# st_v1.net
KiCad netlist of a schematic drawn in Altium Designer
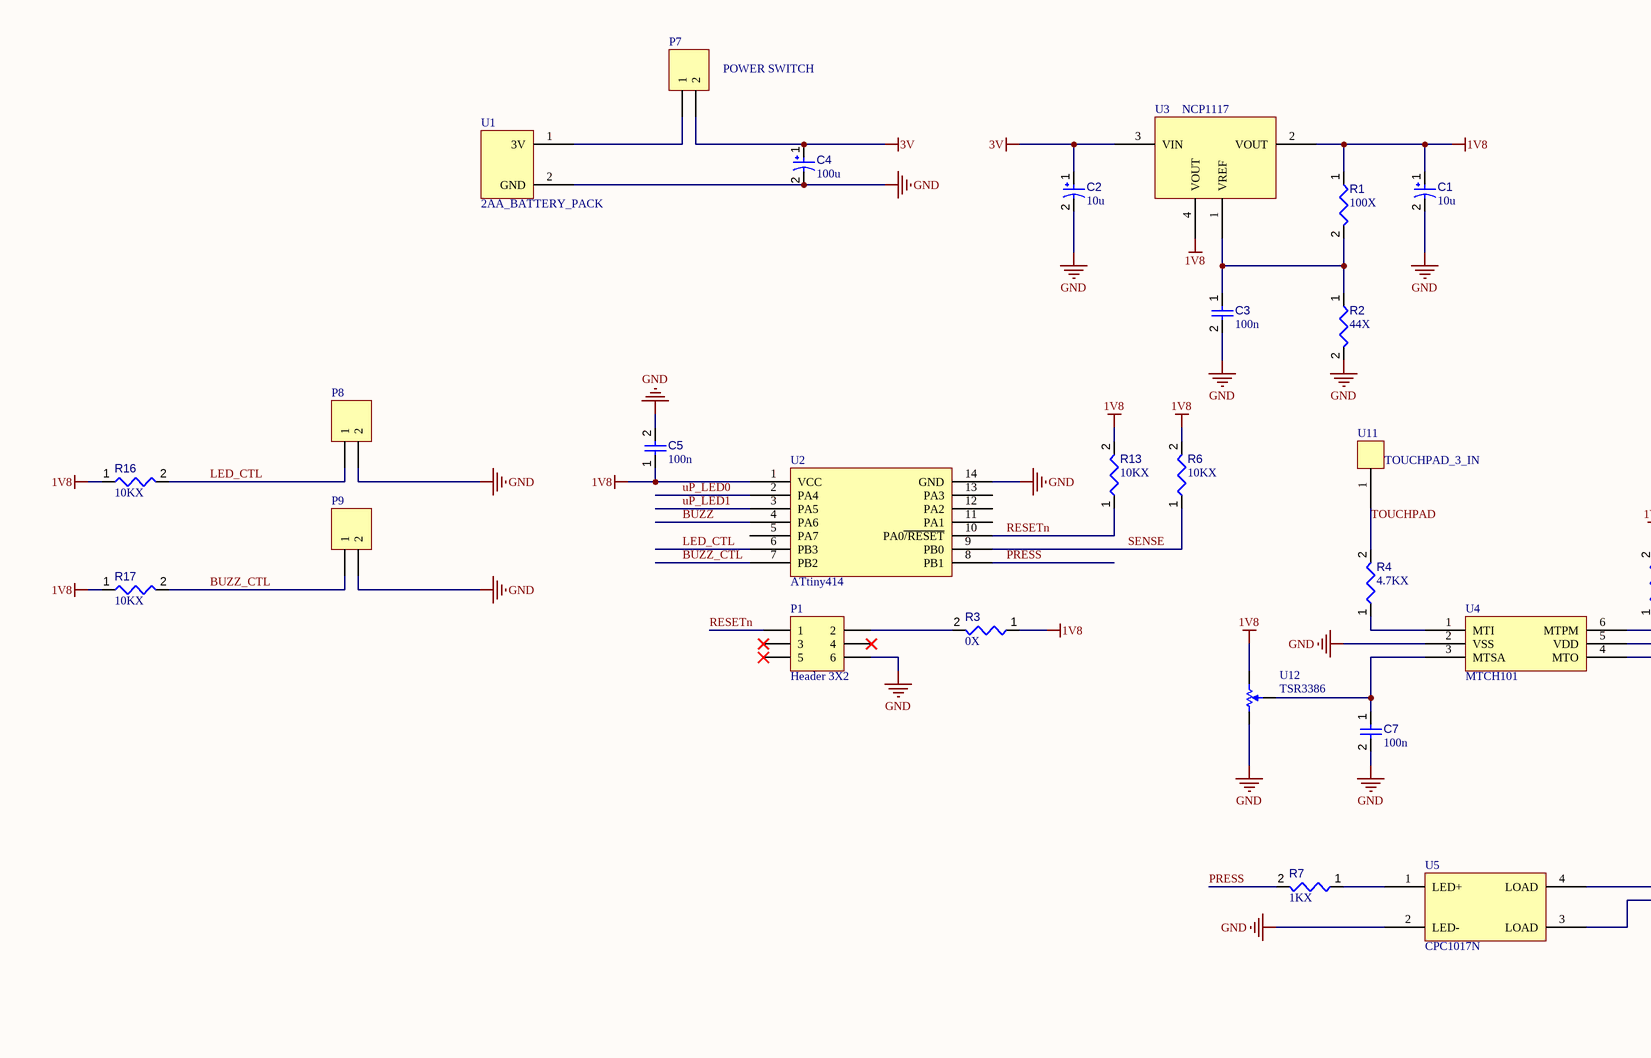
[diagram p0: st_v1.SchDoc, left]
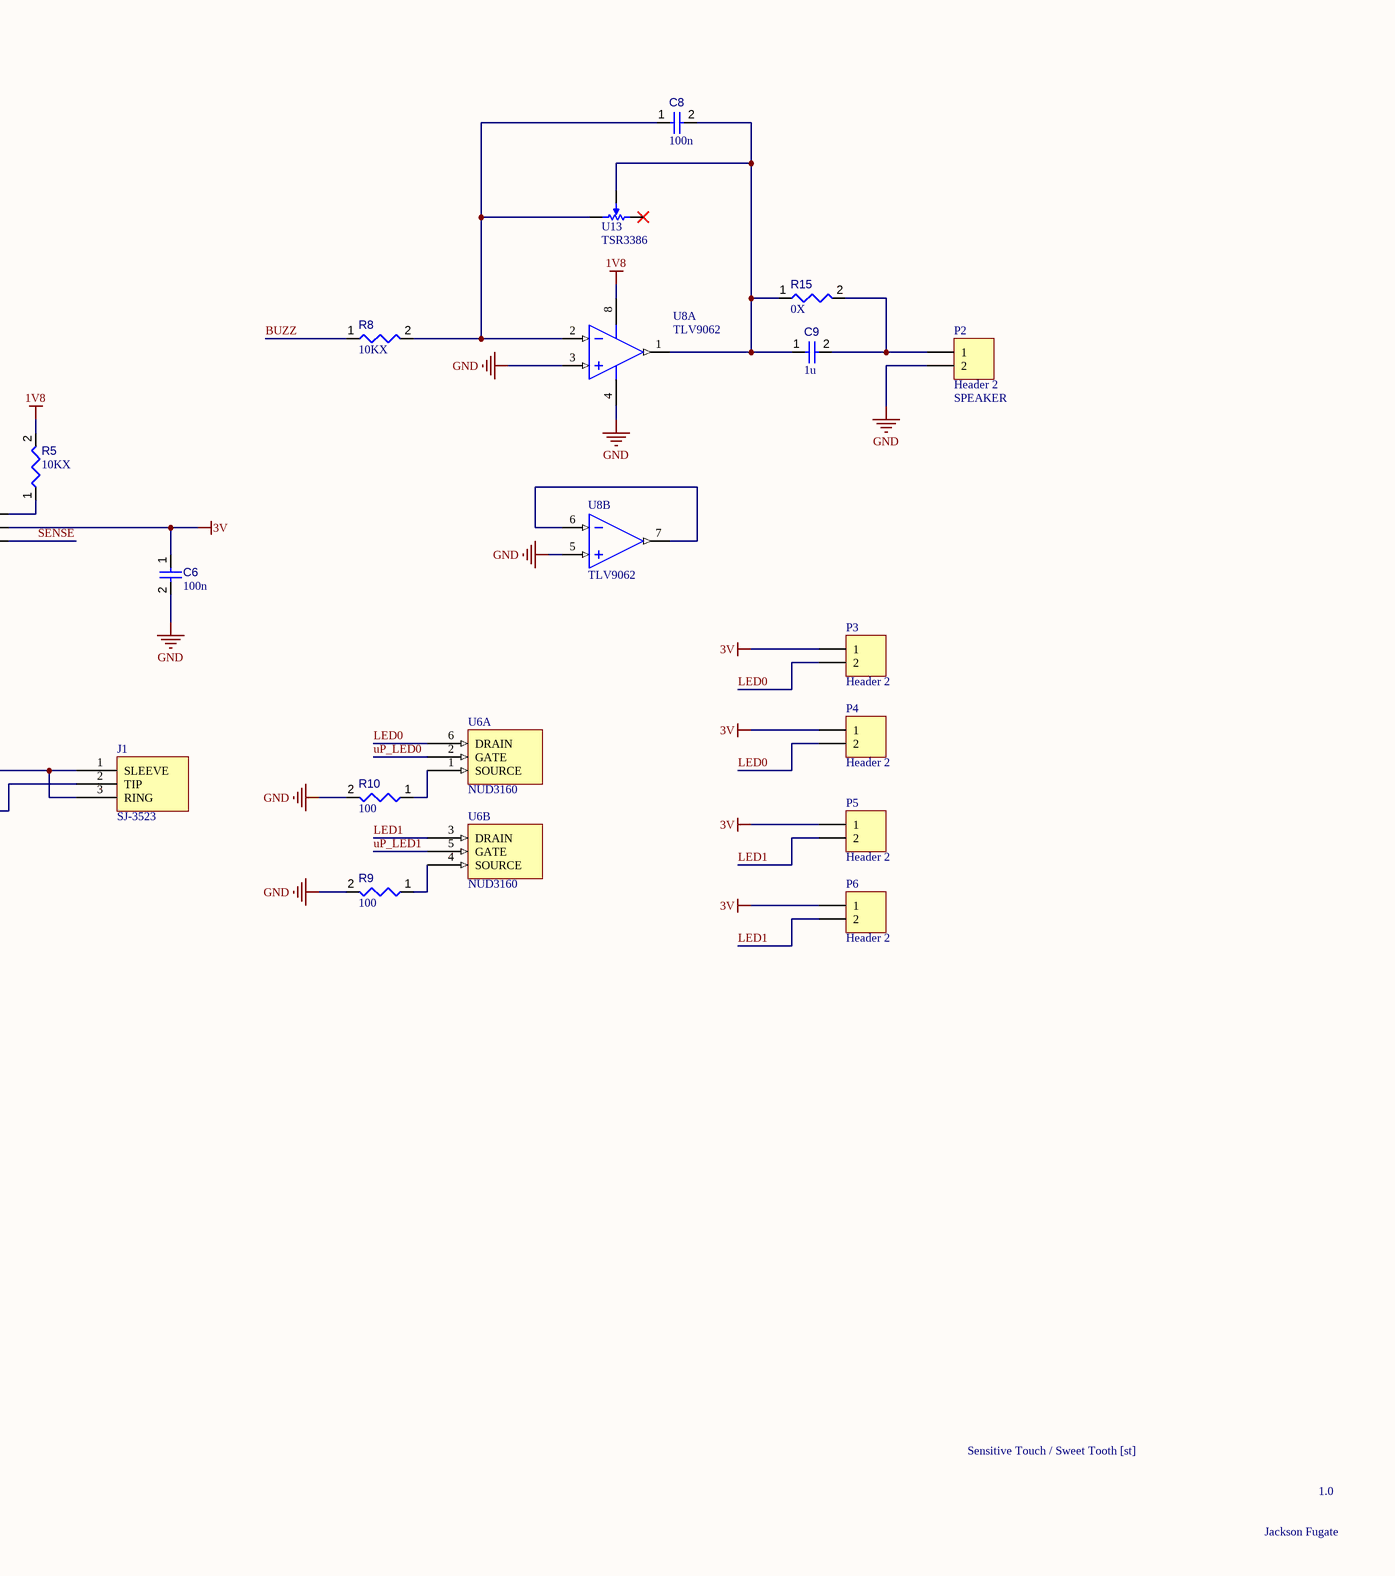
[diagram p1: st_v1.SchDoc, right]

(export (version "E")
  (design (tool "Eeschema 10.0.6"))
  (components
    (comp (ref "C1")
      (value "10u")
      (footprint "CAPPR65-350-1150X800X1250")
      (description "Aluminum Electrolytic Capacitor, 47 uF, +/- 20%, 100 V, -40 to 85 degC, 2-Pin THD, RoHS, Bulk")
      (fields (field (name "TOLERANCE") "20%") (field (name "MANUFACTURER") "Panasonic"))
      (libsource (lib "Jackson Fugate") (part "CAP-P-2"))
    )
    (comp (ref "C2")
      (value "10u")
      (footprint "CAPPR65-350-1150X800X1250")
      (description "Aluminum Electrolytic Capacitor, 47 uF, +/- 20%, 100 V, -40 to 85 degC, 2-Pin THD, RoHS, Bulk")
      (fields (field (name "TOLERANCE") "20%") (field (name "MANUFACTURER") "Panasonic"))
      (libsource (lib "Jackson Fugate") (part "CAP-P-2"))
    )
    (comp (ref "C3")
      (value "100n")
      (footprint "CAPC2013X135X45NL10T25")
      (description "Chip Capacitor, 10 uF, +/- 10%, 16 V, 0805 (2012 Metric)")
      (fields (field (name "TOLERANCE") "10%") (field (name "Comment") "Capacitor 10 uF +/- 10% 16 V 0805"))
      (libsource (lib "Jackson Fugate") (part "CAP-NP-2"))
    )
    (comp (ref "C4")
      (value "100u")
      (footprint "CAPPR65-350-1150X800X1250")
      (description "Aluminum Electrolytic Capacitor, 47 uF, +/- 20%, 100 V, -40 to 85 degC, 2-Pin THD, RoHS, Bulk")
      (fields (field (name "TOLERANCE") "20%") (field (name "MANUFACTURER") "Panasonic"))
      (libsource (lib "Jackson Fugate") (part "CAP-P-2"))
    )
    (comp (ref "C5")
      (value "100n")
      (footprint "CAPC2013X135X45NL10T25")
      (description "Chip Capacitor, 10 uF, +/- 10%, 16 V, 0805 (2012 Metric)")
      (fields (field (name "TOLERANCE") "10%") (field (name "Comment") "Capacitor 10 uF +/- 10% 16 V 0805"))
      (libsource (lib "Jackson Fugate") (part "CAP-NP-2"))
    )
    (comp (ref "C6")
      (value "100n")
      (footprint "CAPC2013X135X45NL10T25")
      (description "Chip Capacitor, 10 uF, +/- 10%, 16 V, 0805 (2012 Metric)")
      (fields (field (name "TOLERANCE") "10%") (field (name "Comment") "Capacitor 10 uF +/- 10% 16 V 0805"))
      (libsource (lib "Jackson Fugate") (part "CAP-NP-2"))
    )
    (comp (ref "C7")
      (value "100n")
      (footprint "CAPC2013X135X45NL10T25")
      (description "Chip Capacitor, 10 uF, +/- 10%, 16 V, 0805 (2012 Metric)")
      (fields (field (name "TOLERANCE") "10%") (field (name "Comment") "Capacitor 10 uF +/- 10% 16 V 0805"))
      (libsource (lib "Jackson Fugate") (part "CAP-NP-2"))
    )
    (comp (ref "C8")
      (value "100n")
      (footprint "CAPC2013X135X45NL10T25")
      (description "Chip Capacitor, 10 uF, +/- 10%, 16 V, 0805 (2012 Metric)")
      (fields (field (name "TOLERANCE") "10%") (field (name "Comment") "Capacitor 10 uF +/- 10% 16 V 0805"))
      (libsource (lib "Jackson Fugate") (part "CAP-NP-2"))
    )
    (comp (ref "C9")
      (value "1u")
      (footprint "CAPC2013X135X45NL10T25")
      (description "Chip Capacitor, 10 uF, +/- 10%, 16 V, 0805 (2012 Metric)")
      (fields (field (name "TOLERANCE") "10%") (field (name "Comment") "Capacitor 10 uF +/- 10% 16 V 0805"))
      (libsource (lib "Jackson Fugate") (part "CAP-NP-2"))
    )
    (comp (ref "J1")
      (value "SJ-3523")
      (footprint "SJ-352X")
      (libsource (lib "JF_master_lib") (part "SJ-3523"))
    )
    (comp (ref "P1")
      (value "Header 3X2")
      (footprint "HDR2X3")
      (description "Header, 3-Pin, Dual row")
      (fields (field (name "PUBLISHER") "Altium Limited"))
      (libsource (lib "Jackson Fugate") (part "Header 3X2H"))
    )
    (comp (ref "P2")
      (value "Header 2")
      (footprint "HDR1X2")
      (description "Header, 2-Pin")
      (fields (field (name "PUBLISHER") "Altium Limited"))
      (libsource (lib "Jackson Fugate") (part "Header 2H"))
    )
    (comp (ref "P3")
      (value "Header 2")
      (footprint "HDR1X2")
      (description "Header, 2-Pin")
      (fields (field (name "PUBLISHER") "Altium Limited"))
      (libsource (lib "Jackson Fugate") (part "Header 2H"))
    )
    (comp (ref "P4")
      (value "Header 2")
      (footprint "HDR1X2")
      (description "Header, 2-Pin")
      (fields (field (name "PUBLISHER") "Altium Limited"))
      (libsource (lib "Jackson Fugate") (part "Header 2H"))
    )
    (comp (ref "P5")
      (value "Header 2")
      (footprint "HDR1X2")
      (description "Header, 2-Pin")
      (fields (field (name "PUBLISHER") "Altium Limited"))
      (libsource (lib "Jackson Fugate") (part "Header 2H"))
    )
    (comp (ref "P6")
      (value "Header 2")
      (footprint "HDR1X2")
      (description "Header, 2-Pin")
      (fields (field (name "PUBLISHER") "Altium Limited"))
      (libsource (lib "Jackson Fugate") (part "Header 2H"))
    )
    (comp (ref "P7")
      (value "POWER SWITCH")
      (footprint "HDR1X2")
      (description "Header, 2-Pin")
      (fields (field (name "PUBLISHER") "Altium Limited"))
      (libsource (lib "") (part "Header 2H_1"))
    )
    (comp (ref "P8")
      (value "POWER SWITCH")
      (footprint "HDR1X2")
      (description "Header, 2-Pin")
      (fields (field (name "PUBLISHER") "Altium Limited"))
      (libsource (lib "") (part "Header 2H_1"))
    )
    (comp (ref "P9")
      (value "POWER SWITCH")
      (footprint "HDR1X2")
      (description "Header, 2-Pin")
      (fields (field (name "PUBLISHER") "Altium Limited"))
      (libsource (lib "") (part "Header 2H_1"))
    )
    (comp (ref "R1")
      (value "100X")
      (footprint "RESC0805(2012)_L")
      (description "1K 0.125W 5% 0805 (2012 Metric)  SMD")
      (fields (field (name "POWER") "0.125W") (field (name "TOLERANCE") "5%"))
      (libsource (lib "Jackson Fugate") (part "1KR5J"))
    )
    (comp (ref "R2")
      (value "44X")
      (footprint "RESC0805(2012)_L")
      (description "1K 0.125W 5% 0805 (2012 Metric)  SMD")
      (fields (field (name "POWER") "0.125W") (field (name "TOLERANCE") "5%"))
      (libsource (lib "Jackson Fugate") (part "1KR5J"))
    )
    (comp (ref "R3")
      (value "0X")
      (footprint "RESC0805(2012)_L")
      (description "1K 0.125W 5% 0805 (2012 Metric)  SMD")
      (fields (field (name "POWER") "0.125W") (field (name "TOLERANCE") "5%"))
      (libsource (lib "Jackson Fugate") (part "1KR5J"))
    )
    (comp (ref "R4")
      (value "4.7KX")
      (footprint "RESC0805(2012)_L")
      (description "1K 0.125W 5% 0805 (2012 Metric)  SMD")
      (fields (field (name "POWER") "0.125W") (field (name "TOLERANCE") "5%"))
      (libsource (lib "Jackson Fugate") (part "1KR5J"))
    )
    (comp (ref "R5")
      (value "10KX")
      (footprint "RESC0805(2012)_L")
      (description "1K 0.125W 5% 0805 (2012 Metric)  SMD")
      (fields (field (name "POWER") "0.125W") (field (name "TOLERANCE") "5%"))
      (libsource (lib "Jackson Fugate") (part "1KR5J"))
    )
    (comp (ref "R6")
      (value "10KX")
      (footprint "RESC0805(2012)_L")
      (description "1K 0.125W 5% 0805 (2012 Metric)  SMD")
      (fields (field (name "POWER") "0.125W") (field (name "TOLERANCE") "5%"))
      (libsource (lib "Jackson Fugate") (part "1KR5J"))
    )
    (comp (ref "R7")
      (value "1KX")
      (footprint "RESC0805(2012)_L")
      (description "1K 0.125W 5% 0805 (2012 Metric)  SMD")
      (fields (field (name "POWER") "0.125W") (field (name "TOLERANCE") "5%"))
      (libsource (lib "Jackson Fugate") (part "1KR5J"))
    )
    (comp (ref "R8")
      (value "10KX")
      (footprint "RESC0805(2012)_L")
      (description "1K 0.125W 5% 0805 (2012 Metric)  SMD")
      (fields (field (name "POWER") "0.125W") (field (name "TOLERANCE") "5%"))
      (libsource (lib "Jackson Fugate") (part "1KR5J"))
    )
    (comp (ref "R9")
      (value "100")
      (footprint "RESC0805(2012)_L")
      (description "1K 0.125W 5% 0805 (2012 Metric)  SMD")
      (fields (field (name "POWER") "0.125W") (field (name "TOLERANCE") "5%"))
      (libsource (lib "Jackson Fugate") (part "1KR5J"))
    )
    (comp (ref "R10")
      (value "100")
      (footprint "RESC0805(2012)_L")
      (description "1K 0.125W 5% 0805 (2012 Metric)  SMD")
      (fields (field (name "POWER") "0.125W") (field (name "TOLERANCE") "5%"))
      (libsource (lib "Jackson Fugate") (part "1KR5J"))
    )
    (comp (ref "R13")
      (value "10KX")
      (footprint "RESC0805(2012)_L")
      (description "1K 0.125W 5% 0805 (2012 Metric)  SMD")
      (fields (field (name "POWER") "0.125W") (field (name "TOLERANCE") "5%"))
      (libsource (lib "Jackson Fugate") (part "1KR5J"))
    )
    (comp (ref "R15")
      (value "0X")
      (footprint "RESC0805(2012)_L")
      (description "1K 0.125W 5% 0805 (2012 Metric)  SMD")
      (fields (field (name "POWER") "0.125W") (field (name "TOLERANCE") "5%"))
      (libsource (lib "Jackson Fugate") (part "1KR5J"))
    )
    (comp (ref "R16")
      (value "10KX")
      (footprint "RESC0805(2012)_L")
      (description "1K 0.125W 5% 0805 (2012 Metric)  SMD")
      (fields (field (name "POWER") "0.125W") (field (name "TOLERANCE") "5%"))
      (libsource (lib "Jackson Fugate") (part "1KR5J"))
    )
    (comp (ref "R17")
      (value "10KX")
      (footprint "RESC0805(2012)_L")
      (description "1K 0.125W 5% 0805 (2012 Metric)  SMD")
      (fields (field (name "POWER") "0.125W") (field (name "TOLERANCE") "5%"))
      (libsource (lib "Jackson Fugate") (part "1KR5J"))
    )
    (comp (ref "U1")
      (value "2AA_BATTERY_PACK")
      (footprint "2AA_BATTERY_PACK")
      (libsource (lib "JF_master_lib") (part "2AA_BATTERY_PACK"))
    )
    (comp (ref "U2")
      (value "ATtiny414")
      (footprint "SOIC-14")
      (libsource (lib "JF_master_lib") (part "ATtiny414"))
    )
    (comp (ref "U3")
      (value "NCP1117")
      (footprint "SOT-223")
      (libsource (lib "JF_master_lib") (part "NCP1117"))
    )
    (comp (ref "U4")
      (value "MTCH101")
      (footprint "SOT-23-6")
      (libsource (lib "JF_master_lib") (part "MTCH101"))
    )
    (comp (ref "U5")
      (value "CPC1017N")
      (footprint "CPC1017N")
      (libsource (lib "JF_master_lib") (part "CPC1017N"))
    )
    (comp (ref "U6") (value "NUD3160") (footprint "SC-74") (libsource (lib "JF_master_lib") (part "NUD3160")))
    (comp (ref "U8")
      (value "TLV9062")
      (footprint "SOIC-8")
      (libsource (lib "JF_master_lib") (part "TLV9062"))
    )
    (comp (ref "U11")
      (value "TOUCHPAD_3_IN")
      (footprint "TOUCHPAD_3_IN")
      (libsource (lib "JF_master_lib") (part "TOUCHPAD_3_IN"))
    )
    (comp (ref "U12")
      (value "TSR3386")
      (footprint "TSR3386")
      (libsource (lib "JF_master_lib") (part "TSR3386"))
    )
    (comp (ref "U13")
      (value "TSR3386")
      (footprint "TSR3386")
      (libsource (lib "JF_master_lib") (part "TSR3386"))
    )
  )
  (nets
    (net (code "1") (name "/BUZZ") (class "Default")
      (node (ref "R8") (pin "1") (pinfunction "1_1") (pintype "passive"))
      (node (ref "U2") (pin "4") (pinfunction "PA6_4") (pintype "passive"))
    )
    (net (code "2") (name "/BUZZ_CTL") (class "Default")
      (node (ref "P9") (pin "1") (pinfunction "1_1") (pintype "passive"))
      (node (ref "R17") (pin "2") (pinfunction "2_2") (pintype "passive"))
      (node (ref "U2") (pin "7") (pinfunction "PB2_7") (pintype "passive"))
    )
    (net (code "3") (name "/LED0") (class "Default")
      (node (ref "P3") (pin "2") (pinfunction "2_2") (pintype "passive"))
      (node (ref "P4") (pin "2") (pinfunction "2_2") (pintype "passive"))
      (node (ref "U6") (pin "6") (pinfunction "DRAIN_6") (pintype "input"))
    )
    (net (code "4") (name "/LED1") (class "Default")
      (node (ref "P5") (pin "2") (pinfunction "2_2") (pintype "passive"))
      (node (ref "P6") (pin "2") (pinfunction "2_2") (pintype "passive"))
      (node (ref "U6") (pin "3") (pinfunction "DRAIN_3") (pintype "input"))
    )
    (net (code "5") (name "/LED_CTL") (class "Default")
      (node (ref "P8") (pin "1") (pinfunction "1_1") (pintype "passive"))
      (node (ref "R16") (pin "2") (pinfunction "2_2") (pintype "passive"))
      (node (ref "U2") (pin "6") (pinfunction "PB3_6") (pintype "passive"))
    )
    (net (code "6") (name "/PRESS") (class "Default")
      (node (ref "R7") (pin "2") (pinfunction "2_2") (pintype "passive"))
      (node (ref "U2") (pin "8") (pinfunction "PB1_8") (pintype "passive"))
    )
    (net (code "7") (name "/RESETn") (class "Default")
      (node (ref "P1") (pin "1") (pinfunction "1_1") (pintype "passive"))
      (node (ref "R13") (pin "1") (pinfunction "1_1") (pintype "passive"))
      (node (ref "U2") (pin "10") (pinfunction "PA0~{/RESET}_10") (pintype "passive"))
    )
    (net (code "8") (name "/SENSE") (class "Default")
      (node (ref "R6") (pin "1") (pinfunction "1_1") (pintype "passive"))
      (node (ref "U2") (pin "9") (pinfunction "PB0_9") (pintype "passive"))
      (node (ref "U4") (pin "4") (pinfunction "MTO_4") (pintype "passive"))
    )
    (net (code "9") (name "/TOUCHPAD") (class "Default")
      (node (ref "R4") (pin "2") (pinfunction "2_2") (pintype "passive"))
      (node (ref "U11") (pin "1") (pintype "passive"))
    )
    (net (code "10") (name "/uP_LED0") (class "Default")
      (node (ref "U2") (pin "2") (pinfunction "PA4_2") (pintype "passive"))
      (node (ref "U6") (pin "2") (pinfunction "GATE_2") (pintype "input"))
    )
    (net (code "11") (name "/uP_LED1") (class "Default")
      (node (ref "U2") (pin "3") (pinfunction "PA5_3") (pintype "passive"))
      (node (ref "U6") (pin "5") (pinfunction "GATE_5") (pintype "input"))
    )
    (net (code "12") (name "1V8") (class "Default")
      (node (ref "C1") (pin "1") (pinfunction "1_1") (pintype "passive"))
      (node (ref "C5") (pin "1") (pinfunction "1_1") (pintype "passive"))
      (node (ref "R1") (pin "1") (pinfunction "1_1") (pintype "passive"))
      (node (ref "R13") (pin "2") (pinfunction "2_2") (pintype "passive"))
      (node (ref "R16") (pin "1") (pinfunction "1_1") (pintype "passive"))
      (node (ref "R17") (pin "1") (pinfunction "1_1") (pintype "passive"))
      (node (ref "R3") (pin "1") (pinfunction "1_1") (pintype "passive"))
      (node (ref "R5") (pin "2") (pinfunction "2_2") (pintype "passive"))
      (node (ref "R6") (pin "2") (pinfunction "2_2") (pintype "passive"))
      (node (ref "U12") (pin "1") (pinfunction "B_1") (pintype "passive"))
      (node (ref "U2") (pin "1") (pinfunction "VCC_1") (pintype "power_in"))
      (node (ref "U3") (pin "2") (pinfunction "VOUT_2") (pintype "power_in"))
      (node (ref "U3") (pin "4") (pinfunction "VOUT_4") (pintype "power_in"))
      (node (ref "U8") (pin "8") (pinfunction "V+_8") (pintype "power_in"))
    )
    (net (code "13") (name "3V") (class "Default")
      (node (ref "C2") (pin "1") (pinfunction "1_1") (pintype "passive"))
      (node (ref "C4") (pin "1") (pinfunction "1_1") (pintype "passive"))
      (node (ref "C6") (pin "1") (pinfunction "1_1") (pintype "passive"))
      (node (ref "P3") (pin "1") (pinfunction "1_1") (pintype "passive"))
      (node (ref "P4") (pin "1") (pinfunction "1_1") (pintype "passive"))
      (node (ref "P5") (pin "1") (pinfunction "1_1") (pintype "passive"))
      (node (ref "P6") (pin "1") (pinfunction "1_1") (pintype "passive"))
      (node (ref "P7") (pin "2") (pinfunction "2_2") (pintype "passive"))
      (node (ref "U3") (pin "3") (pinfunction "VIN_3") (pintype "power_in"))
      (node (ref "U4") (pin "5") (pinfunction "VDD_5") (pintype "power_in"))
    )
    (net (code "14") (name "GND") (class "Default")
      (node (ref "C1") (pin "2") (pinfunction "2_2") (pintype "passive"))
      (node (ref "C2") (pin "2") (pinfunction "2_2") (pintype "passive"))
      (node (ref "C3") (pin "2") (pinfunction "2_2") (pintype "passive"))
      (node (ref "C4") (pin "2") (pinfunction "2_2") (pintype "passive"))
      (node (ref "C5") (pin "2") (pinfunction "2_2") (pintype "passive"))
      (node (ref "C6") (pin "2") (pinfunction "2_2") (pintype "passive"))
      (node (ref "C7") (pin "2") (pinfunction "2_2") (pintype "passive"))
      (node (ref "P1") (pin "6") (pinfunction "6_6") (pintype "passive"))
      (node (ref "P2") (pin "2") (pinfunction "2_2") (pintype "passive"))
      (node (ref "P8") (pin "2") (pinfunction "2_2") (pintype "passive"))
      (node (ref "P9") (pin "2") (pinfunction "2_2") (pintype "passive"))
      (node (ref "R10") (pin "2") (pinfunction "2_2") (pintype "passive"))
      (node (ref "R2") (pin "2") (pinfunction "2_2") (pintype "passive"))
      (node (ref "R9") (pin "2") (pinfunction "2_2") (pintype "passive"))
      (node (ref "U1") (pin "2") (pinfunction "GND_2") (pintype "power_in"))
      (node (ref "U12") (pin "3") (pinfunction "A_3") (pintype "passive"))
      (node (ref "U2") (pin "14") (pinfunction "GND_14") (pintype "power_in"))
      (node (ref "U4") (pin "2") (pinfunction "VSS_2") (pintype "power_in"))
      (node (ref "U5") (pin "2") (pinfunction "LED-_2") (pintype "passive"))
      (node (ref "U8") (pin "3") (pinfunction "+IN_3") (pintype "input"))
      (node (ref "U8") (pin "4") (pinfunction "V-_4") (pintype "power_in"))
      (node (ref "U8") (pin "5") (pinfunction "+IN_5") (pintype "input"))
    )
    (net (code "15") (name "Net-(C9-Pad2)") (class "Default")
      (node (ref "C9") (pin "2") (pinfunction "2_2") (pintype "passive"))
      (node (ref "P2") (pin "1") (pinfunction "1_1") (pintype "passive"))
      (node (ref "R15") (pin "2") (pinfunction "2_2") (pintype "passive"))
    )
    (net (code "16") (name "Net-(J1-RING)") (class "Default")
      (node (ref "J1") (pin "1") (pinfunction "SLEEVE_1") (pintype "passive"))
      (node (ref "J1") (pin "3") (pinfunction "RING_3") (pintype "passive"))
      (node (ref "U5") (pin "4") (pinfunction "LOAD_4") (pintype "passive"))
    )
    (net (code "17") (name "Net-(J1-TIP)") (class "Default")
      (node (ref "J1") (pin "2") (pinfunction "TIP_2") (pintype "passive"))
      (node (ref "U5") (pin "3") (pinfunction "LOAD_3") (pintype "passive"))
    )
    (net (code "18") (name "Net-(P1-Pad2)") (class "Default")
      (node (ref "P1") (pin "2") (pinfunction "2_2") (pintype "passive"))
      (node (ref "R3") (pin "2") (pinfunction "2_2") (pintype "passive"))
    )
    (net (code "19") (name "Net-(U1-3V)") (class "Default")
      (node (ref "P7") (pin "1") (pinfunction "1_1") (pintype "passive"))
      (node (ref "U1") (pin "1") (pinfunction "3V_1") (pintype "power_in"))
    )
    (net (code "20") (name "Net-(U3-VREF)") (class "Default")
      (node (ref "C3") (pin "1") (pinfunction "1_1") (pintype "passive"))
      (node (ref "R1") (pin "2") (pinfunction "2_2") (pintype "passive"))
      (node (ref "R2") (pin "1") (pinfunction "1_1") (pintype "passive"))
      (node (ref "U3") (pin "1") (pinfunction "VREF_1") (pintype "power_in"))
    )
    (net (code "21") (name "Net-(U4-MTI)") (class "Default")
      (node (ref "R4") (pin "1") (pinfunction "1_1") (pintype "passive"))
      (node (ref "U4") (pin "1") (pinfunction "MTI_1") (pintype "passive"))
    )
    (net (code "22") (name "Net-(U4-MTPM)") (class "Default")
      (node (ref "R5") (pin "1") (pinfunction "1_1") (pintype "passive"))
      (node (ref "U4") (pin "6") (pinfunction "MTPM_6") (pintype "passive"))
    )
    (net (code "23") (name "Net-(U5-LED+)") (class "Default")
      (node (ref "R7") (pin "1") (pinfunction "1_1") (pintype "passive"))
      (node (ref "U5") (pin "1") (pinfunction "LED+_1") (pintype "passive"))
    )
    (net (code "24") (name "Net-(U6A-SOURCE)") (class "Default")
      (node (ref "R10") (pin "1") (pinfunction "1_1") (pintype "passive"))
      (node (ref "U6") (pin "1") (pinfunction "SOURCE_1") (pintype "input"))
    )
    (net (code "25") (name "Net-(U6B-SOURCE)") (class "Default")
      (node (ref "R9") (pin "1") (pinfunction "1_1") (pintype "passive"))
      (node (ref "U6") (pin "4") (pinfunction "SOURCE_4") (pintype "input"))
    )
    (net (code "26") (name "Net-(U8B--IN)") (class "Default")
      (node (ref "U8") (pin "6") (pinfunction "-IN_6") (pintype "input"))
      (node (ref "U8") (pin "7") (pinfunction "OUT_7") (pintype "output"))
    )
    (net (code "27") (name "Net-(U12-TAP)") (class "Default")
      (node (ref "C7") (pin "1") (pinfunction "1_1") (pintype "passive"))
      (node (ref "U12") (pin "2") (pinfunction "TAP_2") (pintype "passive"))
      (node (ref "U4") (pin "3") (pinfunction "MTSA_3") (pintype "passive"))
    )
    (net (code "28") (name "Net-(U13-B)") (class "Default")
      (node (ref "C8") (pin "1") (pinfunction "1_1") (pintype "passive"))
      (node (ref "R8") (pin "2") (pinfunction "2_2") (pintype "passive"))
      (node (ref "U13") (pin "1") (pinfunction "B_1") (pintype "passive"))
      (node (ref "U8") (pin "2") (pinfunction "-IN_2") (pintype "input"))
    )
    (net (code "29") (name "Net-(U13-TAP)") (class "Default")
      (node (ref "C8") (pin "2") (pinfunction "2_2") (pintype "passive"))
      (node (ref "C9") (pin "1") (pinfunction "1_1") (pintype "passive"))
      (node (ref "R15") (pin "1") (pinfunction "1_1") (pintype "passive"))
      (node (ref "U13") (pin "2") (pinfunction "TAP_2") (pintype "passive"))
      (node (ref "U8") (pin "1") (pinfunction "OUT_1") (pintype "output"))
    )
    (net (code "30") (name "unconnected-(P1-Pad3)") (class "Default")
      (node (ref "P1") (pin "3") (pinfunction "3_3") (pintype "passive+no_connect"))
    )
    (net (code "31") (name "unconnected-(P1-Pad4)") (class "Default")
      (node (ref "P1") (pin "4") (pinfunction "4_4") (pintype "passive+no_connect"))
    )
    (net (code "32") (name "unconnected-(P1-Pad5)") (class "Default")
      (node (ref "P1") (pin "5") (pinfunction "5_5") (pintype "passive+no_connect"))
    )
    (net (code "33") (name "unconnected-(U2-PA1-Pad11)") (class "Default")
      (node (ref "U2") (pin "11") (pinfunction "PA1_11") (pintype "passive"))
    )
    (net (code "34") (name "unconnected-(U2-PA2-Pad12)") (class "Default")
      (node (ref "U2") (pin "12") (pinfunction "PA2_12") (pintype "passive"))
    )
    (net (code "35") (name "unconnected-(U2-PA3-Pad13)") (class "Default")
      (node (ref "U2") (pin "13") (pinfunction "PA3_13") (pintype "passive"))
    )
    (net (code "36") (name "unconnected-(U2-PA7-Pad5)") (class "Default")
      (node (ref "U2") (pin "5") (pinfunction "PA7_5") (pintype "passive"))
    )
    (net (code "37") (name "unconnected-(U13-A-Pad3)") (class "Default")
      (node (ref "U13") (pin "3") (pinfunction "A_3") (pintype "passive+no_connect"))
    )
  )
)
